# POWER_BLOCK.net
KiCad netlist of a schematic drawn in Altium Designer
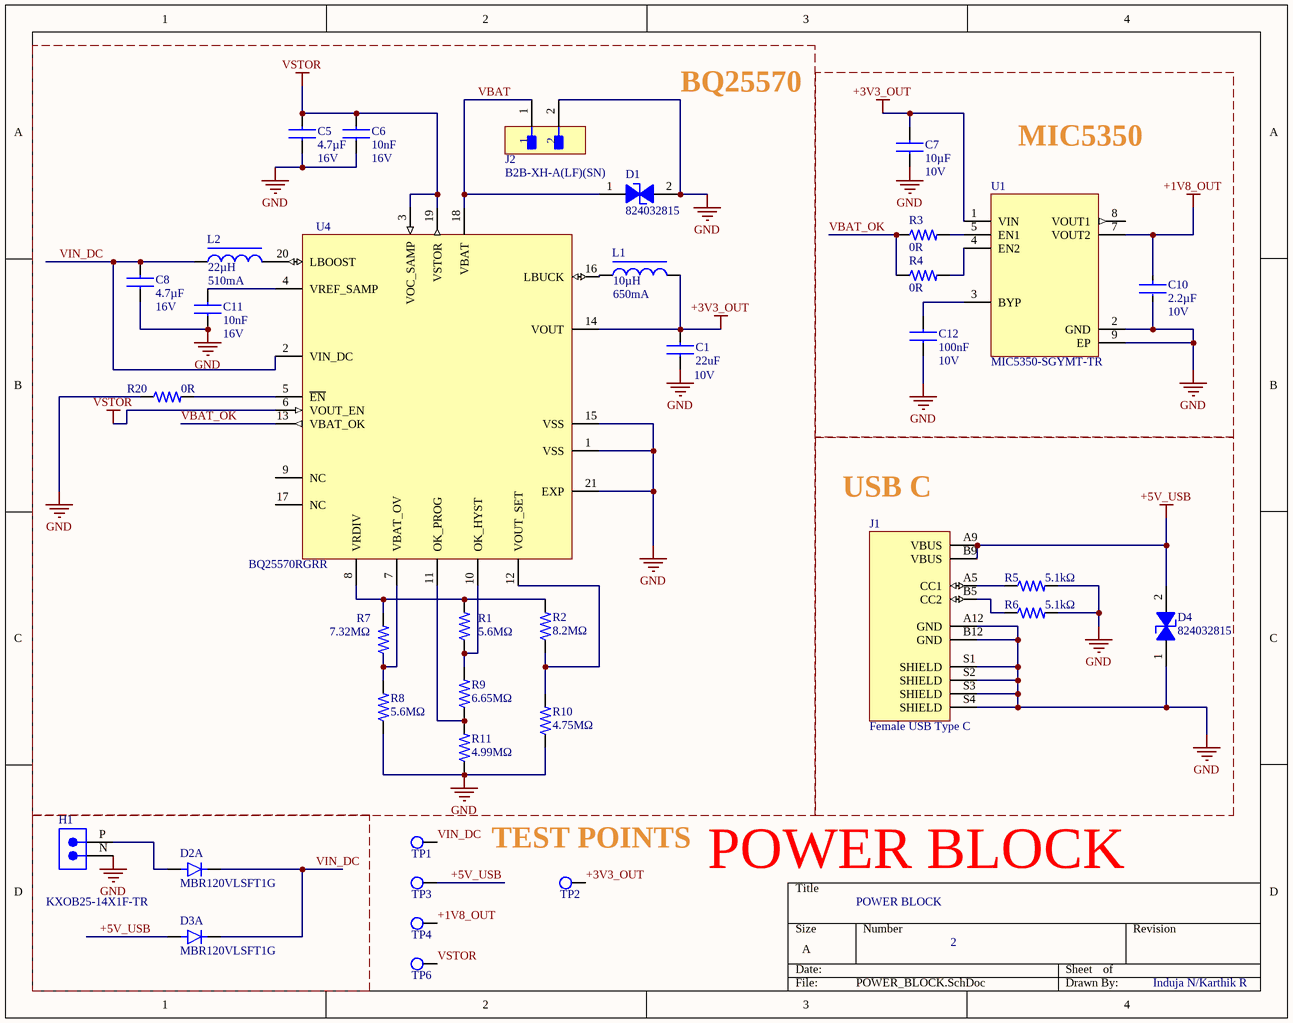
[diagram p0: POWER_BLOCK.SchDoc]

(export (version "E")
  (design (tool "Eeschema 10.0.6"))
  (components
    (comp (ref "C1")
      (value "22uF")
      (footprint "Capacitor 0603")
      (description "CAP CER 22UF 10V X5R 0603")
      (fields
        (field (name "MANUFACTURER") "Murata")
        (field (name "MANUFACTURER PART NUMBER") "GRM188R61A226ME15D")
        (field (name "VOLTAGE RATING DC") "10V")
      )
      (libsource (lib "LPEDT_Components") (part "GRM188R61A226ME15D"))
    )
    (comp (ref "C5")
      (value "4.7µF")
      (footprint "Capacitor 0603")
      (description "16V 4.7uF X7R ±10% 0603 Multilayer Ceramic Capacitors MLCC - SMD/SMT ROHS")
      (fields
        (field (name "MANUFACTURER") "Murata")
        (field (name "MANUFACTURER PART NUMBER") "GRM188Z71C475KE21D")
        (field (name "VOLTAGE RATING (DC)") "16V")
      )
      (libsource (lib "LPEDT_Components") (part "CAP 4.7uF 16V X7R"))
    )
    (comp (ref "C6")
      (value "10nF")
      (footprint "Capacitor 0603")
      (description "Multilayer Ceramic Capacitors MLCC - SMD/SMT 16V 0.01uF X7R 0603 10% AEC-Q200")
      (fields
        (field (name "MANUFACTURER") "KEMET")
        (field (name "MANUFACTURER PART NUMBER") "C0603C103K4RECAUTO")
        (field (name "VOLTAGE RATING (DC)") "16V")
      )
      (libsource (lib "LPEDT_Components") (part "CAP 10nF 0603"))
    )
    (comp (ref "C7")
      (value "10µF")
      (footprint "CAP_0603_1MM")
      (description "10V 10uF X7R ±10% 0603 Multilayer Ceramic Capacitors MLCC - SMD/SMT ROHS")
      (fields
        (field (name "MANUFACTURER") "Murata")
        (field (name "MANUFACTURER PART NUMBER") "GRM188Z71A106KA73D")
        (field (name "VOLTAGE RATING") "10V")
      )
      (libsource (lib "LPEDT_Components") (part "CAP 10uF 0603"))
    )
    (comp (ref "C8")
      (value "4.7µF")
      (footprint "Capacitor 0603")
      (description "16V 4.7uF X7R ±10% 0603 Multilayer Ceramic Capacitors MLCC - SMD/SMT ROHS")
      (fields
        (field (name "MANUFACTURER") "Murata")
        (field (name "MANUFACTURER PART NUMBER") "GRM188Z71C475KE21D")
        (field (name "VOLTAGE RATING (DC)") "16V")
      )
      (libsource (lib "LPEDT_Components") (part "CAP 4.7uF 16V X7R"))
    )
    (comp (ref "C10")
      (value "2.2µF")
      (footprint "CAP_0603_1MM")
      (description "10V 2.2uF X7R ±10% 0603 Multilayer Ceramic Capacitors MLCC - SMD/SMT ROHS")
      (fields
        (field (name "MANUFACTURER") "Samsung Electro-Mechanics")
        (field (name "MANUFACTURER PART NUMBER") "CL10B225KP8NNNC")
        (field (name "VOLTAGE RATING (DC)") "10V")
      )
      (libsource (lib "LPEDT_Components") (part "CAP 2.2uF 0603"))
    )
    (comp (ref "C11")
      (value "10nF")
      (footprint "Capacitor 0603")
      (description "Multilayer Ceramic Capacitors MLCC - SMD/SMT 16V 0.01uF X7R 0603 10% AEC-Q200")
      (fields
        (field (name "MANUFACTURER") "KEMET")
        (field (name "MANUFACTURER PART NUMBER") "C0603C103K4RECAUTO")
        (field (name "VOLTAGE RATING (DC)") "16V")
      )
      (libsource (lib "LPEDT_Components") (part "CAP 10nF 0603"))
    )
    (comp (ref "C12")
      (value "100nF")
      (footprint "CAP_0603_1MM")
      (description "0603 0.1 uF 10 V ±10% Tolerance X7R SMT Multilayer Ceramic Chip Capacitor")
      (fields
        (field (name "MANUFACTURER") "Vishay")
        (field (name "MANUFACTURER PART NUMBER") "VJ0603Y104KXQCW1BC")
        (field (name "VOLTAGE RATING (DC)") "10V")
      )
      (libsource (lib "LPEDT_Components") (part "CAP 0.1uF 0603"))
    )
    (comp (ref "D1")
      (value "824032815")
      (footprint "WE-TVS_DFN1610-2L")
      (description "824032815 Tvs Diode, Bidir, 5V, Dfn1610 Rohs Compliant: Yes ¦Wurth Elektronik 824032815")
      (libsource (lib "LPEDT_Components") (part "TVS Diode ESD Protection"))
    )
    (comp (ref "D2")
      (value "MBR120VLSFT1G")
      (footprint "ONSC-SOD-123FL-2-498-01_V")
      (description "Schottky Power Rectifier, 2-Pin SOD-123, Pb-Free, Tape and Reel")
      (fields (field (name "MANUFACTURER") "On Semiconductor"))
      (libsource (lib "LPEDT_Components") (part "Diode Schottky"))
    )
    (comp (ref "D3")
      (value "MBR120VLSFT1G")
      (footprint "ONSC-SOD-123FL-2-498-01_V")
      (description "Schottky Power Rectifier, 2-Pin SOD-123, Pb-Free, Tape and Reel")
      (fields (field (name "MANUFACTURER") "On Semiconductor"))
      (libsource (lib "LPEDT_Components") (part "Diode Schottky"))
    )
    (comp (ref "D4")
      (value "824032815")
      (footprint "WE-TVS_DFN1610-2L")
      (description "824032815 Tvs Diode, Bidir, 5V, Dfn1610 Rohs Compliant: Yes ¦Wurth Elektronik 824032815")
      (libsource (lib "LPEDT_Components") (part "TVS Diode ESD Protection"))
    )
    (comp (ref "H1")
      (value "KXOB25-14X1F-TR")
      (footprint "SOLAR CELL")
      (description "MONOCRYS SOLAR CELL 30.7MW 690MV")
      (fields
        (field (name "MANUFACTURER") "Sullins")
        (field (name "MANUFACTURER PART NUMBER") "PRPC002SAAN-RC")
      )
      (libsource (lib "LPEDT_Components") (part "SOLAR_CELL"))
    )
    (comp (ref "J1")
      (value "Female USB Type C")
      (footprint "GCT_USB4125-GF-A_REVA2")
      (fields (field (name "MANUFACTURER PART NUMBER") "USB4125-GF-A_REVA2"))
      (libsource (lib "LPEDT_Components") (part "USB-C Power Connector"))
    )
    (comp (ref "J2")
      (value "B2B-XH-A(LF)(SN)")
      (footprint "FP-B2B-XH-A_LF_SN-MFG")
      (description "CONN HEADER VERT 2POS 2.5MM")
      (libsource (lib "LPEDT_Components") (part "CMP-2000-05888-3"))
    )
    (comp (ref "L1")
      (value "744029100")
      (footprint "WE-TPC_2813")
      (description "10 µH Shielded Drum Core, Wirewound Inductor 650 mA 470mOhm Max Nonstandard")
      (fields
        (field (name "TOLERANCE") "30%")
        (field (name "INDUCTANCE") "10µH")
        (field (name "CURRENT RATING") "650mA")
      )
      (libsource (lib "LPEDT_Components") (part "CMP-0227-00077-3"))
    )
    (comp (ref "L2")
      (value "744031220")
      (footprint "WE-TPC_3816")
      (description "22 µH Shielded Drum Core, Wirewound Inductor 510 mA 450mOhm Max Nonstandard")
      (fields
        (field (name "CURRENT RATING") "510mA")
        (field (name "TOLERANCE") "30%")
        (field (name "INDUCTANCE") "22µH")
      )
      (libsource (lib "LPEDT_Components") (part "CMP-0227-00346-4"))
    )
    (comp (ref "R1")
      (value "5.6MΩ")
      (footprint "RES_0603_1608X06")
      (description "1.24 MOhms ±1% 0.125W, 1/8W Chip Resistor 0603 (1608 Metric) Automotive AEC-Q200 Thick Film")
      (fields
        (field (name "MANUFACTURER") "Yageo")
        (field (name "MANUFACTURER PART NUMBER") "RC0603JR-075M6L")
      )
      (libsource (lib "LPEDT_Components") (part "RES 1.24M 0603"))
    )
    (comp (ref "R2")
      (value "8.2MΩ")
      (footprint "RES_0603_1608X06")
      (fields
        (field (name "MANUFACTURER") "Yageo")
        (field (name "MANUFACTURER PART NUMBER") "RC0603JR-078M2L")
        (field (name "TOLERANCE") "5%")
      )
      (libsource (lib "LPEDT_Components") (part "RES 8.2M 0603"))
    )
    (comp (ref "R3")
      (value "0R")
      (footprint "RES_0603_1608X06")
      (description "GENERAL PURPOSE CHIP RESISTOR Metal Glaze/thick Film, 0.1W, 0ohm, Surface Mount, 0603")
      (fields
        (field (name "MANUFACTURER") "Yageo Group")
        (field (name "MANUFACTURER PART NUMBER") "RC0603JR-070RL")
      )
      (libsource (lib "LPEDT_Components") (part "RES 0R 0603"))
    )
    (comp (ref "R4")
      (value "0R")
      (footprint "RES_0603_1608X06")
      (description "GENERAL PURPOSE CHIP RESISTOR Metal Glaze/thick Film, 0.1W, 0ohm, Surface Mount, 0603")
      (fields
        (field (name "MANUFACTURER") "Yageo Group")
        (field (name "MANUFACTURER PART NUMBER") "RC0603JR-070RL")
      )
      (libsource (lib "LPEDT_Components") (part "RES 0R 0603"))
    )
    (comp (ref "R5")
      (value "5.1kΩ")
      (footprint "RES_0603_1608X06")
      (fields
        (field (name "MANUFACTURER") "Yageo")
        (field (name "MANUFACTURER PART NUMBER") "RC0603FR-075K1L")
        (field (name "TOLERANCE") "1%")
      )
      (libsource (lib "LPEDT_Components") (part "RES 5.1K 0603"))
    )
    (comp (ref "R6")
      (value "5.1kΩ")
      (footprint "RES_0603_1608X06")
      (fields
        (field (name "MANUFACTURER") "Yageo")
        (field (name "MANUFACTURER PART NUMBER") "RC0603FR-075K1L")
        (field (name "TOLERANCE") "1%")
      )
      (libsource (lib "LPEDT_Components") (part "RES 5.1K 0603"))
    )
    (comp (ref "R7")
      (value "7.32MΩ")
      (footprint "RES_0603_1608X06")
      (fields
        (field (name "MANUFACTURER") "Yageo")
        (field (name "MANUFACTURER PART NUMBER") "RC0402FR-077M32L")
        (field (name "TOLERANCE") "1%")
      )
      (libsource (lib "LPEDT_Components") (part "RES 7.32M 0603"))
    )
    (comp (ref "R8")
      (value "5.6MΩ")
      (footprint "RES_0603_1608X06")
      (fields
        (field (name "MANUFACTURER") "Yageo")
        (field (name "MANUFACTURER PART NUMBER") "RC0603JR-075M6L")
        (field (name "TOLERANCE") "5%")
      )
      (libsource (lib "LPEDT_Components") (part "RES 5.62M 0603"))
    )
    (comp (ref "R9")
      (value "6.65MΩ")
      (footprint "RES_0603_1608X06")
      (description "Res Thick Film 0603 6.65M Ohm 1% 0.1W(1/10W) ±200ppm/C Pad SMD T/R Automotive AEC-Q200")
      (fields
        (field (name "MANUFACTURER") "Stackpole Electronics")
        (field (name "MANUFACTURER PART NUMBER") "RMCF0603FT6M65")
      )
      (libsource (lib "LPEDT_Components") (part "RES 6.65M 0603"))
    )
    (comp (ref "R10")
      (value "4.75MΩ")
      (footprint "RES_0603_1608X06")
      (fields
        (field (name "MANUFACTURER") "Yageo")
        (field (name "MANUFACTURER PART NUMBER") "RC0603FR-074M75L")
        (field (name "TOLERANCE") "1%")
      )
      (libsource (lib "LPEDT_Components") (part "RES 4.75M 0603"))
    )
    (comp (ref "R11")
      (value "4.99MΩ")
      (footprint "RES_0603_1608X06")
      (fields
        (field (name "MANUFACTURER") "Yageo")
        (field (name "MANUFACTURER PART NUMBER") "RC0603FR-074M99L")
        (field (name "TOLERANCE") "1%")
      )
      (libsource (lib "LPEDT_Components") (part "RES 4.99M 0603"))
    )
    (comp (ref "R20")
      (value "0R")
      (footprint "RES_0603_1608X06")
      (description "GENERAL PURPOSE CHIP RESISTOR Metal Glaze/thick Film, 0.1W, 0ohm, Surface Mount, 0603")
      (fields
        (field (name "MANUFACTURER") "Yageo Group")
        (field (name "MANUFACTURER PART NUMBER") "RC0603JR-070RL")
      )
      (libsource (lib "LPEDT_Components") (part "RES 0R 0603"))
    )
    (comp (ref "TP1")
      (value "Test Point")
      (footprint "Test Point")
      (libsource (lib "LPEDT_Components") (part "Test Point"))
    )
    (comp (ref "TP2")
      (value "Test Point")
      (footprint "Test Point")
      (libsource (lib "LPEDT_Components") (part "Test Point"))
    )
    (comp (ref "TP3")
      (value "Test Point")
      (footprint "Test Point")
      (libsource (lib "LPEDT_Components") (part "Test Point"))
    )
    (comp (ref "TP4")
      (value "Test Point")
      (footprint "Test Point")
      (libsource (lib "LPEDT_Components") (part "Test Point"))
    )
    (comp (ref "TP6")
      (value "Test Point")
      (footprint "Test Point")
      (libsource (lib "LPEDT_Components") (part "Test Point"))
    )
    (comp (ref "U1")
      (value "MIC5350-SGYMT-TR")
      (footprint "SON50P200X200X60-9N")
      (description "Linear Voltage Regulator IC Positive Fixed 2 Output 300mA, 500mA 8-TMLFÂ® (2x2)")
      (fields (field (name "MF") "Microchip"))
      (libsource (lib "LPEDT_Components") (part "MIC5350-SGYMT-TR"))
    )
    (comp (ref "U4")
      (value "BQ25570RGRR")
      (footprint "QFN50P350X350X100-21N")
      (description "Ultra Low power Harvester power Management IC with boost charger, and Nanopower Buck Converter")
      (fields (field (name "MF") "Texas Instruments"))
      (libsource (lib "LPEDT_Components") (part "BQ25570RGRR"))
    )
  )
  (nets
    (net (code "1") (name "+1V8_OUT") (class "Default")
      (node (ref "C10") (pin "1") (pinfunction "1_1") (pintype "passive"))
      (node (ref "TP4") (pin "1") (pinfunction "1_1") (pintype "passive"))
      (node (ref "U1") (pin "7") (pinfunction "VOUT2_7") (pintype "power_in"))
    )
    (net (code "2") (name "+3V3_OUT") (class "Default")
      (node (ref "C1") (pin "2") (pinfunction "2_2") (pintype "passive"))
      (node (ref "C7") (pin "1") (pinfunction "1_1") (pintype "passive"))
      (node (ref "L1") (pin "2") (pinfunction "2_2") (pintype "passive"))
      (node (ref "TP2") (pin "1") (pinfunction "1_1") (pintype "passive"))
      (node (ref "U1") (pin "1") (pinfunction "VIN_1") (pintype "power_in"))
      (node (ref "U4") (pin "14") (pinfunction "VOUT_14") (pintype "power_in"))
    )
    (net (code "3") (name "+5V_USB") (class "Default")
      (node (ref "D3") (pin "1") (pinfunction "1_1") (pintype "passive"))
      (node (ref "D4") (pin "2") (pinfunction "GND_2") (pintype "passive"))
      (node (ref "J1") (pin "A9") (pinfunction "VBUS_A9") (pintype "power_in"))
      (node (ref "TP3") (pin "1") (pinfunction "1_1") (pintype "passive"))
    )
    (net (code "5") (name "/VBAT") (class "Default")
      (node (ref "D1") (pin "1") (pinfunction "I/O_1_1") (pintype "passive"))
      (node (ref "J2") (pin "1") (pinfunction "1_1") (pintype "passive"))
      (node (ref "U4") (pin "18") (pinfunction "VBAT_18") (pintype "power_in"))
    )
    (net (code "6") (name "/VBAT_OK") (class "Default")
      (node (ref "R3") (pin "1") (pinfunction "1_1") (pintype "passive"))
      (node (ref "R4") (pin "1") (pinfunction "1_1") (pintype "passive"))
      (node (ref "U4") (pin "13") (pinfunction "VBAT_OK_13") (pintype "output"))
    )
    (net (code "7") (name "/VIN_DC") (class "Default")
      (node (ref "C8") (pin "1") (pinfunction "1_1") (pintype "passive"))
      (node (ref "D2") (pin "2") (pinfunction "2_2") (pintype "passive"))
      (node (ref "D3") (pin "2") (pinfunction "2_2") (pintype "passive"))
      (node (ref "L2") (pin "1") (pinfunction "1_1") (pintype "passive"))
      (node (ref "TP1") (pin "1") (pinfunction "1_1") (pintype "passive"))
      (node (ref "U4") (pin "2") (pinfunction "VIN_DC_2") (pintype "passive"))
    )
    (net (code "8") (name "GND") (class "Default")
      (node (ref "C1") (pin "1") (pinfunction "1_1") (pintype "passive"))
      (node (ref "C10") (pin "2") (pinfunction "2_2") (pintype "passive"))
      (node (ref "C11") (pin "2") (pinfunction "2_2") (pintype "passive"))
      (node (ref "C12") (pin "2") (pinfunction "2_2") (pintype "passive"))
      (node (ref "C5") (pin "2") (pinfunction "2_2") (pintype "passive"))
      (node (ref "C6") (pin "2") (pinfunction "2_2") (pintype "passive"))
      (node (ref "C7") (pin "2") (pinfunction "2_2") (pintype "passive"))
      (node (ref "C8") (pin "2") (pinfunction "2_2") (pintype "passive"))
      (node (ref "D1") (pin "2") (pinfunction "GND_2") (pintype "passive"))
      (node (ref "D4") (pin "1") (pinfunction "I/O_1_1") (pintype "passive"))
      (node (ref "H1") (pin "N") (pinfunction "2_N") (pintype "passive"))
      (node (ref "J1") (pin "A12") (pinfunction "GND_A12") (pintype "passive"))
      (node (ref "J1") (pin "B12") (pinfunction "GND_B12") (pintype "passive"))
      (node (ref "J1") (pin "S1") (pinfunction "SHIELD_S1") (pintype "passive"))
      (node (ref "J1") (pin "S2") (pinfunction "SHIELD_S2") (pintype "passive"))
      (node (ref "J1") (pin "S3") (pinfunction "SHIELD_S3") (pintype "passive"))
      (node (ref "J1") (pin "S4") (pinfunction "SHIELD_S4") (pintype "passive"))
      (node (ref "J2") (pin "2") (pinfunction "2_2") (pintype "passive"))
      (node (ref "R10") (pin "1") (pinfunction "1_1") (pintype "passive"))
      (node (ref "R11") (pin "1") (pinfunction "1_1") (pintype "passive"))
      (node (ref "R20") (pin "1") (pinfunction "1_1") (pintype "passive"))
      (node (ref "R5") (pin "2") (pinfunction "2_2") (pintype "passive"))
      (node (ref "R6") (pin "2") (pinfunction "2_2") (pintype "passive"))
      (node (ref "R8") (pin "1") (pinfunction "1_1") (pintype "passive"))
      (node (ref "U1") (pin "2") (pinfunction "GND_2") (pintype "passive"))
      (node (ref "U1") (pin "9") (pinfunction "EP_9") (pintype "passive"))
      (node (ref "U4") (pin "1") (pinfunction "VSS_1") (pintype "power_in"))
      (node (ref "U4") (pin "15") (pinfunction "VSS_15") (pintype "power_in"))
      (node (ref "U4") (pin "21") (pinfunction "EXP_21") (pintype "passive"))
    )
    (net (code "9") (name "Net-(H1-1)") (class "Default")
      (node (ref "D2") (pin "1") (pinfunction "1_1") (pintype "passive"))
      (node (ref "H1") (pin "P") (pinfunction "1_P") (pintype "power_in"))
    )
    (net (code "10") (name "Net-(J1-CC1)") (class "Default")
      (node (ref "J1") (pin "A5") (pinfunction "CC1_A5") (pintype "bidirectional"))
      (node (ref "R5") (pin "1") (pinfunction "1_1") (pintype "passive"))
    )
    (net (code "11") (name "Net-(J1-CC2)") (class "Default")
      (node (ref "J1") (pin "B5") (pinfunction "CC2_B5") (pintype "bidirectional"))
      (node (ref "R6") (pin "1") (pinfunction "1_1") (pintype "passive"))
    )
    (net (code "12") (name "Net-(U1-BYP)") (class "Default")
      (node (ref "C12") (pin "1") (pinfunction "1_1") (pintype "passive"))
      (node (ref "U1") (pin "3") (pinfunction "BYP_3") (pintype "passive"))
    )
    (net (code "13") (name "Net-(U1-EN1)") (class "Default")
      (node (ref "R3") (pin "2") (pinfunction "2_2") (pintype "passive"))
      (node (ref "U1") (pin "5") (pinfunction "EN1_5") (pintype "passive"))
    )
    (net (code "14") (name "Net-(U1-EN2)") (class "Default")
      (node (ref "R4") (pin "2") (pinfunction "2_2") (pintype "passive"))
      (node (ref "U1") (pin "4") (pinfunction "EN2_4") (pintype "passive"))
    )
    (net (code "15") (name "Net-(U4-LBOOST)") (class "Default")
      (node (ref "L2") (pin "2") (pinfunction "2_2") (pintype "passive"))
      (node (ref "U4") (pin "20") (pinfunction "LBOOST_20") (pintype "bidirectional"))
    )
    (net (code "16") (name "Net-(U4-LBUCK)") (class "Default")
      (node (ref "L1") (pin "1") (pinfunction "1_1") (pintype "passive"))
      (node (ref "U4") (pin "16") (pinfunction "LBUCK_16") (pintype "bidirectional"))
    )
    (net (code "17") (name "Net-(U4-OK_HYST)") (class "Default")
      (node (ref "R1") (pin "1") (pinfunction "1_1") (pintype "passive"))
      (node (ref "R9") (pin "2") (pinfunction "2_2") (pintype "passive"))
      (node (ref "U4") (pin "10") (pinfunction "OK_HYST_10") (pintype "passive"))
    )
    (net (code "18") (name "Net-(U4-OK_PROG)") (class "Default")
      (node (ref "R11") (pin "2") (pinfunction "2_2") (pintype "passive"))
      (node (ref "R9") (pin "1") (pinfunction "1_1") (pintype "passive"))
      (node (ref "U4") (pin "11") (pinfunction "OK_PROG_11") (pintype "passive"))
    )
    (net (code "19") (name "Net-(U4-VBAT_OV)") (class "Default")
      (node (ref "R7") (pin "1") (pinfunction "1_1") (pintype "passive"))
      (node (ref "R8") (pin "2") (pinfunction "2_2") (pintype "passive"))
      (node (ref "U4") (pin "7") (pinfunction "VBAT_OV_7") (pintype "passive"))
    )
    (net (code "20") (name "Net-(U4-VOUT_SET)") (class "Default")
      (node (ref "R10") (pin "2") (pinfunction "2_2") (pintype "passive"))
      (node (ref "R2") (pin "1") (pinfunction "1_1") (pintype "passive"))
      (node (ref "U4") (pin "12") (pinfunction "VOUT_SET_12") (pintype "passive"))
    )
    (net (code "21") (name "Net-(U4-VRDIV)") (class "Default")
      (node (ref "R1") (pin "2") (pinfunction "2_2") (pintype "passive"))
      (node (ref "R2") (pin "2") (pinfunction "2_2") (pintype "passive"))
      (node (ref "R7") (pin "2") (pinfunction "2_2") (pintype "passive"))
      (node (ref "U4") (pin "8") (pinfunction "VRDIV_8") (pintype "passive"))
    )
    (net (code "22") (name "Net-(U4-VREF_SAMP)") (class "Default")
      (node (ref "C11") (pin "1") (pinfunction "1_1") (pintype "passive"))
      (node (ref "U4") (pin "4") (pinfunction "VREF_SAMP_4") (pintype "passive"))
    )
    (net (code "23") (name "Net-(U4-~{EN})") (class "Default")
      (node (ref "R20") (pin "2") (pinfunction "2_2") (pintype "passive"))
      (node (ref "U4") (pin "5") (pinfunction "~{EN}_5") (pintype "passive"))
    )
    (net (code "24") (name "VSTOR") (class "Default")
      (node (ref "C5") (pin "1") (pinfunction "1_1") (pintype "passive"))
      (node (ref "C6") (pin "1") (pinfunction "1_1") (pintype "passive"))
      (node (ref "TP6") (pin "1") (pinfunction "1_1") (pintype "passive"))
      (node (ref "U4") (pin "19") (pinfunction "VSTOR_19") (pintype "output"))
      (node (ref "U4") (pin "3") (pinfunction "VOC_SAMP_3") (pintype "input"))
      (node (ref "U4") (pin "6") (pinfunction "VOUT_EN_6") (pintype "input"))
    )
    (net (code "25") (name "unconnected-(J1-VBUS-PadB9)") (class "Default")
      (node (ref "J1") (pin "B9") (pinfunction "VBUS_B9") (pintype "power_in"))
    )
    (net (code "26") (name "unconnected-(U1-VOUT1-Pad8)") (class "Default")
      (node (ref "U1") (pin "8") (pinfunction "VOUT1_8") (pintype "output"))
    )
    (net (code "27") (name "unconnected-(U4-NC-Pad9)") (class "Default")
      (node (ref "U4") (pin "9") (pinfunction "NC_9") (pintype "passive"))
    )
    (net (code "28") (name "unconnected-(U4-NC-Pad17)") (class "Default")
      (node (ref "U4") (pin "17") (pinfunction "NC_17") (pintype "passive"))
    )
  )
)
